# YTN1-E608-WIFI_V1_6432.net
KiCad netlist of a schematic drawn in Altium Designer
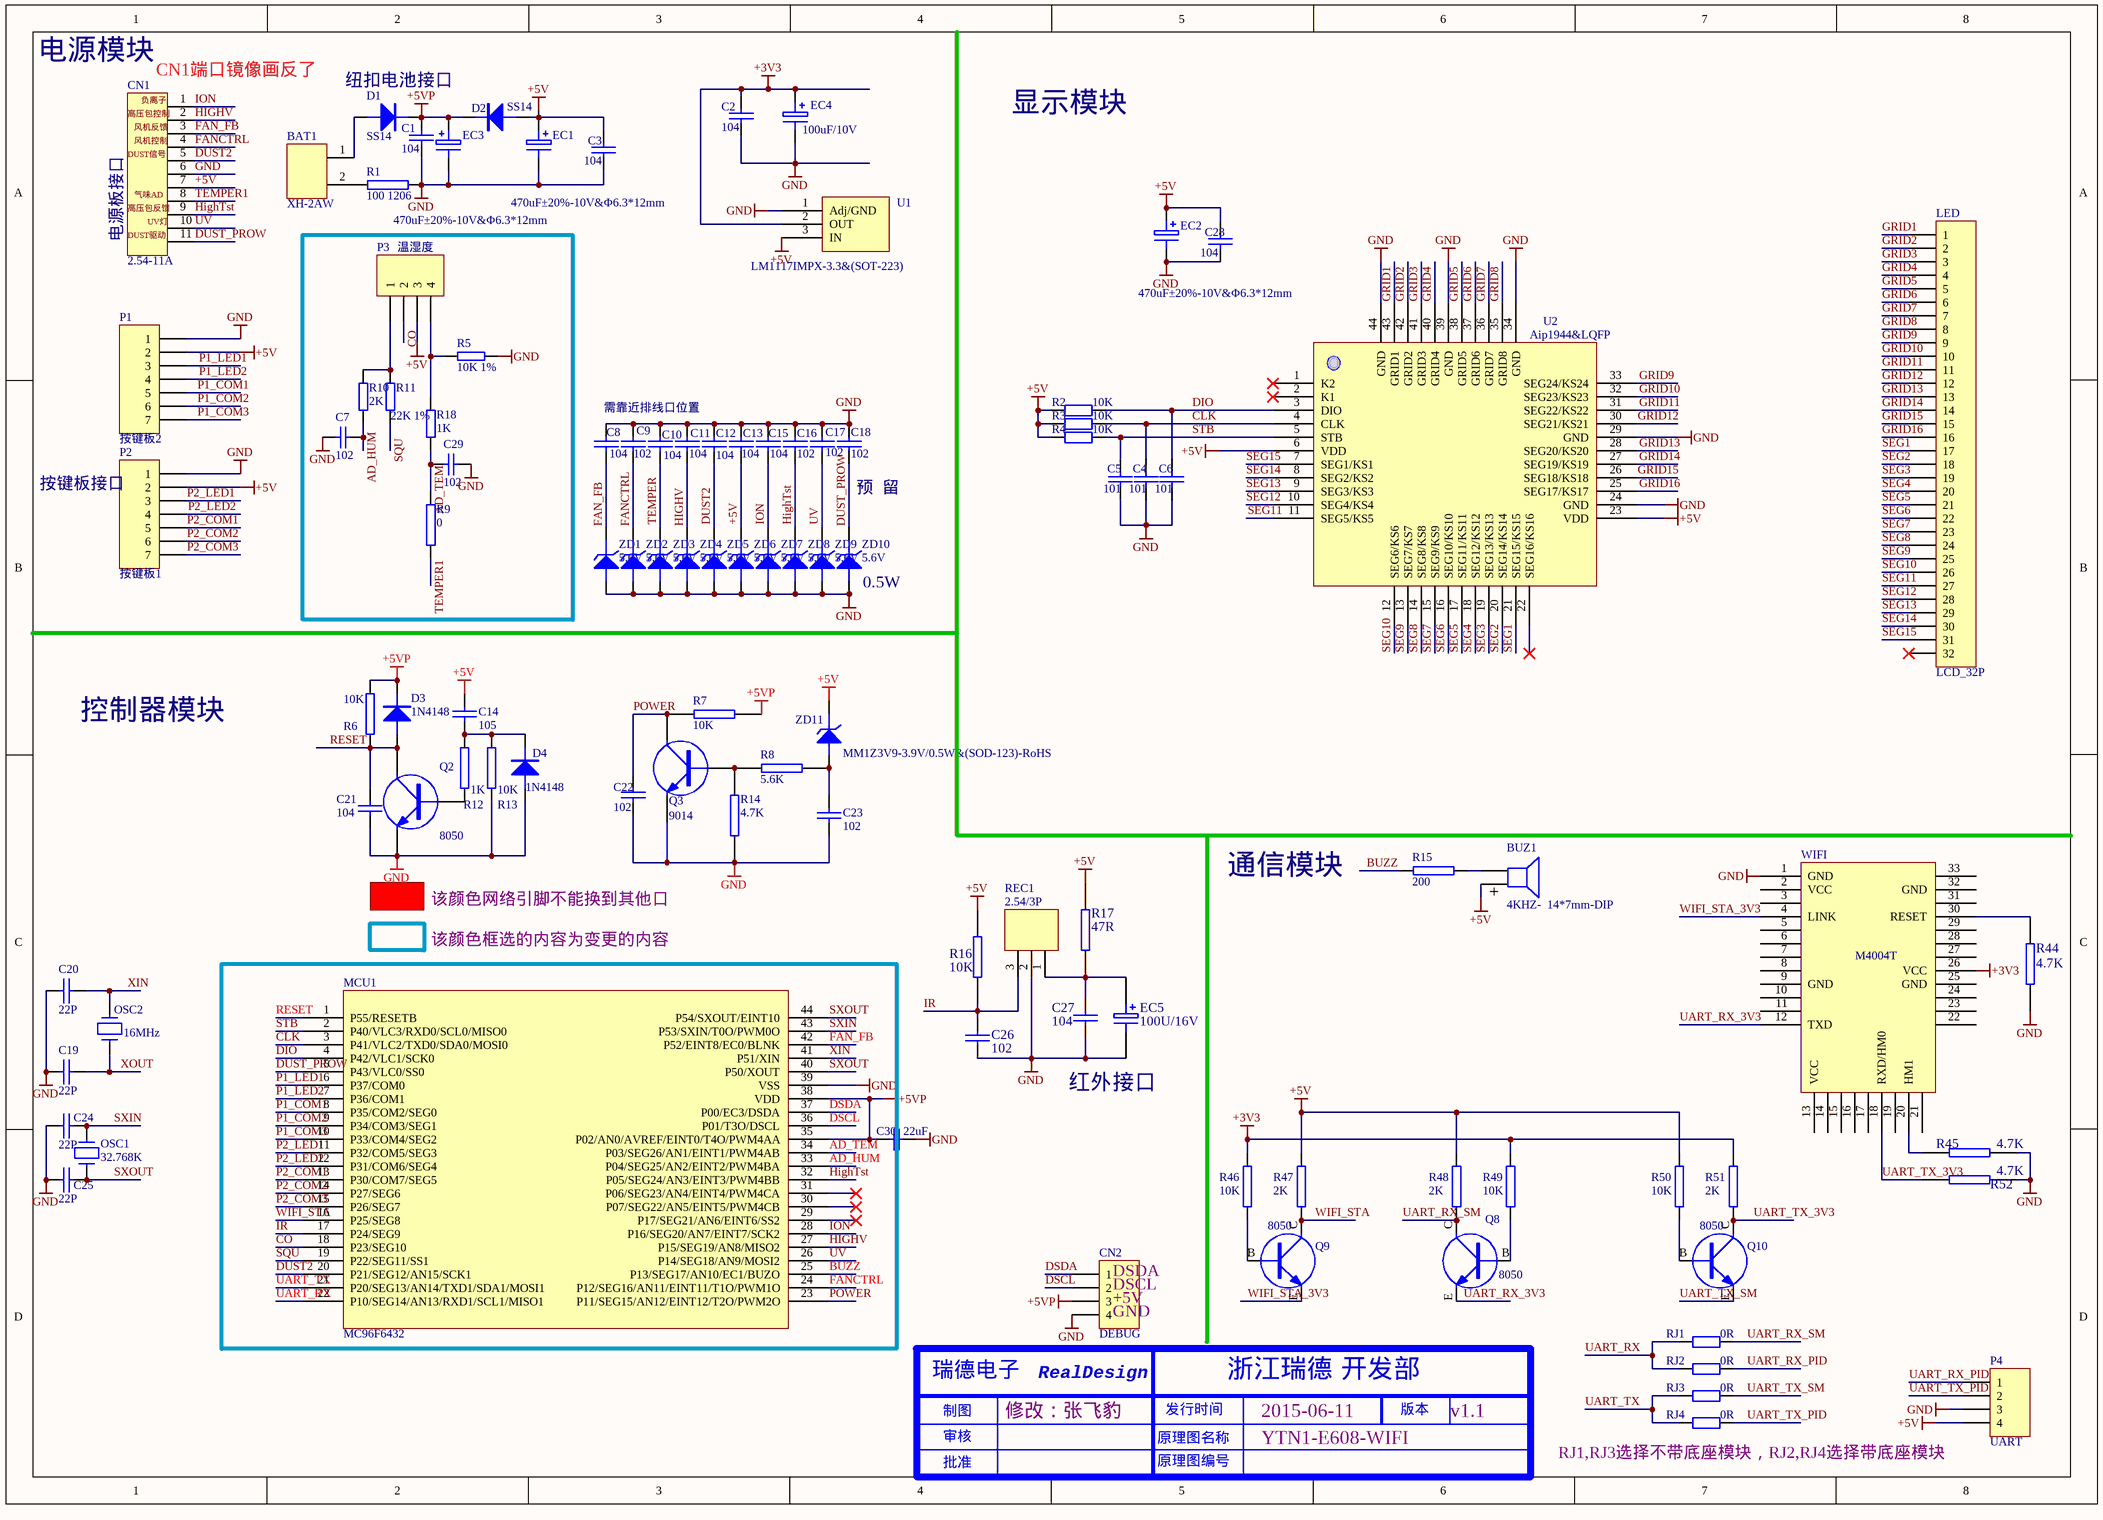
[diagram p0: YTN1-E608-WIFI_V1_6432..schdoc]

(export (version "E")
  (design (tool "Eeschema 10.0.6"))
  (components
    (comp (ref "BAT1") (value "XH-2AW") (footprint "XH-2AW-1") (libsource (lib "*") (part "250-2A")))
    (comp (ref "BUZ1")
      (value "4KHZ-  14*7mm-DIP")
      (footprint "BUZ4K-BCE")
      (libsource (lib "*") (part "SPEAKER"))
    )
    (comp (ref "C1") (value "104") (footprint "0805C") (libsource (lib "*") (part "CAP")))
    (comp (ref "C2") (value "104") (footprint "0805C") (libsource (lib "*") (part "CAP")))
    (comp (ref "C3") (value "104") (footprint "0805C") (libsource (lib "*") (part "CAP")))
    (comp (ref "C4")
      (value "101")
      (footprint "0805C")
      (description "瓷片电容、独石电容")
      (libsource (lib "*") (part "CAP"))
    )
    (comp (ref "C5")
      (value "101")
      (footprint "0805C")
      (description "瓷片电容、独石电容")
      (libsource (lib "*") (part "CAP"))
    )
    (comp (ref "C6")
      (value "101")
      (footprint "0805C")
      (description "瓷片电容、独石电容")
      (libsource (lib "*") (part "CAP"))
    )
    (comp (ref "C7")
      (value "102")
      (footprint "C0805")
      (description "Capacitor")
      (fields (field (name "PUBLISHER") "Altium Limited"))
      (libsource (lib "*") (part "Cap"))
    )
    (comp (ref "C8")
      (value "104")
      (footprint "0805C")
      (description "瓷片电容、独石电容")
      (libsource (lib "*") (part "CAP"))
    )
    (comp (ref "C9")
      (value "102")
      (footprint "0805C")
      (description "瓷片电容、独石电容")
      (libsource (lib "*") (part "CAP"))
    )
    (comp (ref "C10")
      (value "104")
      (footprint "0805C")
      (description "瓷片电容、独石电容")
      (libsource (lib "*") (part "CAP"))
    )
    (comp (ref "C11")
      (value "104")
      (footprint "0805C")
      (description "瓷片电容、独石电容")
      (libsource (lib "*") (part "CAP"))
    )
    (comp (ref "C12")
      (value "104")
      (footprint "0805C")
      (description "瓷片电容、独石电容")
      (libsource (lib "*") (part "CAP"))
    )
    (comp (ref "C13")
      (value "104")
      (footprint "0805C")
      (description "瓷片电容、独石电容")
      (libsource (lib "*") (part "CAP"))
    )
    (comp (ref "C14")
      (value "105")
      (footprint "0805C")
      (description "瓷片电容、独石电容")
      (libsource (lib "*") (part "CAP"))
    )
    (comp (ref "C15")
      (value "104")
      (footprint "0805C")
      (description "瓷片电容、独石电容")
      (libsource (lib "*") (part "CAP"))
    )
    (comp (ref "C16")
      (value "102")
      (footprint "0805C")
      (description "瓷片电容、独石电容")
      (libsource (lib "*") (part "CAP"))
    )
    (comp (ref "C17")
      (value "102")
      (footprint "0805C")
      (description "瓷片电容、独石电容")
      (libsource (lib "*") (part "CAP"))
    )
    (comp (ref "C18")
      (value "102")
      (footprint "0805C")
      (description "瓷片电容、独石电容")
      (libsource (lib "*") (part "CAP"))
    )
    (comp (ref "C19")
      (value "22P")
      (footprint "0805C")
      (description "瓷片电容、独石电容")
      (libsource (lib "") (part "CAP_1"))
    )
    (comp (ref "C20")
      (value "22P")
      (footprint "0805C")
      (description "瓷片电容、独石电容")
      (libsource (lib "") (part "CAP_1"))
    )
    (comp (ref "C21")
      (value "104")
      (footprint "0805C")
      (description "瓷片电容、独石电容")
      (libsource (lib "*") (part "CAP"))
    )
    (comp (ref "C22")
      (value "102")
      (footprint "0805C")
      (description "瓷片电容、独石电容")
      (libsource (lib "*") (part "CAP"))
    )
    (comp (ref "C23")
      (value "102")
      (footprint "0805C")
      (description "瓷片电容、独石电容")
      (libsource (lib "*") (part "CAP"))
    )
    (comp (ref "C24") (value "22P") (footprint "0805C") (libsource (lib "*") (part "CAP")))
    (comp (ref "C25") (value "22P") (footprint "0805C") (libsource (lib "*") (part "CAP")))
    (comp (ref "C26")
      (value "102")
      (footprint "0805C")
      (description "Capacitor")
      (libsource (lib "") (part "CAP_2"))
    )
    (comp (ref "C27")
      (value "104")
      (footprint "0805C")
      (description "Capacitor")
      (libsource (lib "") (part "CAP_2"))
    )
    (comp (ref "C28") (value "104") (footprint "0805C") (libsource (lib "*") (part "CAP")))
    (comp (ref "C29")
      (value "102")
      (footprint "C0805")
      (description "Capacitor")
      (fields (field (name "PUBLISHER") "Altium Limited"))
      (libsource (lib "*") (part "Cap"))
    )
    (comp (ref "C30")
      (value "22uF")
      (footprint "C0805")
      (description "Capacitor")
      (fields (field (name "PUBLISHER") "Altium Limited"))
      (libsource (lib "*") (part "Cap"))
    )
    (comp (ref "CN1") (value "2.54-11A") (footprint "XH-11AW-1") (libsource (lib "*") (part "3.96-11A")))
    (comp (ref "CN2")
      (value "DEBUG")
      (footprint "XH-4AW-1")
      (description "Header, 4-Pin")
      (fields (field (name "PUBLISHER") "Altium Limited"))
      (libsource (lib "*") (part "Header 4"))
    )
    (comp (ref "D1")
      (value "SS14")
      (footprint "SMA")
      (description "整流二极管、开关二极管、肖特基二极管、快恢复二极管")
      (libsource (lib "*") (part "DIODE"))
    )
    (comp (ref "D2")
      (value "SS14")
      (footprint "SMA")
      (description "整流二极管、开关二极管、肖特基二极管、快恢复二极管")
      (libsource (lib "*") (part "DIODE"))
    )
    (comp (ref "D3")
      (value "1N4148")
      (footprint "SOD-123")
      (description "整流二极管、开关二极管、肖特基二极管、快恢复二极管")
      (libsource (lib "*") (part "DIODE"))
    )
    (comp (ref "D4")
      (value "1N4148")
      (footprint "SOD-123")
      (description "整流二极管、开关二极管、肖特基二极管、快恢复二极管")
      (libsource (lib "*") (part "DIODE"))
    )
    (comp (ref "EC1")
      (value "470uF±20%-10V&Φ6.3*12mm")
      (footprint "470UF10V-AI")
      (description "电解电容正极为\"1\"号脚")
      (libsource (lib "*") (part "ELECTRO"))
    )
    (comp (ref "EC2")
      (value "470uF±20%-10V&Φ6.3*12mm")
      (footprint "470UF10V-AI")
      (description "电解电容正极为\"1\"号脚")
      (libsource (lib "*") (part "ELECTRO"))
    )
    (comp (ref "EC3")
      (value "470uF±20%-10V&Φ6.3*12mm")
      (footprint "470UF10V-AI")
      (libsource (lib "*") (part "ELECTRO1"))
    )
    (comp (ref "EC4") (value "100uF/10V") (footprint "100UF10V-AI") (libsource (lib "*") (part "ELECTRO1")))
    (comp (ref "EC5")
      (value "100U/16V")
      (footprint "100UF16V-AI")
      (description "Electrolytic Capacitor")
      (libsource (lib "") (part "ELECTRO1_1"))
    )
    (comp (ref "LED") (value "LCD_32P") (footprint "HYH") (libsource (lib "*") (part "LCD_32P")))
    (comp (ref "MCU1") (value "MC96F6432") (footprint "QFP44-2") (libsource (lib "*") (part "MC96F9432")))
    (comp (ref "OSC1")
      (value "32.768K")
      (footprint "32.768J")
      (description "Crystal")
      (libsource (lib "") (part "CRYSTAL_1"))
    )
    (comp (ref "OSC2")
      (value "16MHz")
      (footprint "CSA4.19MG")
      (description "Crystal")
      (libsource (lib "*") (part "CRYSTAL"))
    )
    (comp (ref "P1")
      (value "按键板2")
      (footprint "XH-7AW-1")
      (description "Header, 7-Pin")
      (fields (field (name "PUBLISHER") "Altium Limited"))
      (libsource (lib "*") (part "Header 7"))
    )
    (comp (ref "P2")
      (value "按键板1")
      (footprint "XH-7AW-1")
      (description "Header, 7-Pin")
      (fields (field (name "PUBLISHER") "Altium Limited"))
      (libsource (lib "*") (part "Header 7"))
    )
    (comp (ref "P3")
      (value "温湿度")
      (footprint "HDR1X4")
      (description "Header, 4-Pin")
      (fields (field (name "PUBLISHER") "Altium Limited"))
      (libsource (lib "") (part "Header 4_1"))
    )
    (comp (ref "P4")
      (value "UART")
      (footprint "XH-4AW-1")
      (description "Header, 4-Pin")
      (fields (field (name "PUBLISHER") "Altium Limited"))
      (libsource (lib "*") (part "Header 4"))
    )
    (comp (ref "Q2")
      (value "8050")
      (footprint "SOT-23-S")
      (description "晶体管")
      (libsource (lib "*") (part "NPN"))
    )
    (comp (ref "Q3")
      (value "9014")
      (footprint "SOT-23-S")
      (description "晶体管")
      (libsource (lib "*") (part "NPN"))
    )
    (comp (ref "Q8")
      (value "8050")
      (footprint "SOT-23-S")
      (description "NPN Transistor")
      (libsource (lib "") (part "NPN_1"))
    )
    (comp (ref "Q9")
      (value "8050")
      (footprint "SOT-23-S")
      (description "NPN Transistor")
      (libsource (lib "") (part "NPN_1"))
    )
    (comp (ref "Q10")
      (value "8050")
      (footprint "SOT-23-S")
      (description "NPN Transistor")
      (libsource (lib "") (part "NPN_1"))
    )
    (comp (ref "R1") (value "100 1206") (footprint "1206R") (libsource (lib "*") (part "RES2")))
    (comp (ref "R2")
      (value "10K")
      (footprint "0805R")
      (description "Resistor")
      (fields (field (name "Comment") "Res2") (field (name "PUBLISHER") "Altium Limited"))
      (libsource (lib "") (part "Res2_1"))
    )
    (comp (ref "R3")
      (value "10K")
      (footprint "0805R")
      (description "Resistor")
      (fields (field (name "Comment") "Res2") (field (name "PUBLISHER") "Altium Limited"))
      (libsource (lib "") (part "Res2_1"))
    )
    (comp (ref "R4")
      (value "10K")
      (footprint "0805R")
      (description "Resistor")
      (fields (field (name "Comment") "Res2") (field (name "PUBLISHER") "Altium Limited"))
      (libsource (lib "*") (part "Res2"))
    )
    (comp (ref "R5")
      (value "10K 1%")
      (footprint "0805r")
      (description "RESISTOR")
      (libsource (lib "") (part "RES2_V_1"))
    )
    (comp (ref "R6") (value "10K") (footprint "0805R") (libsource (lib "*") (part "RES2")))
    (comp (ref "R7") (value "10K") (footprint "0805R") (libsource (lib "*") (part "R")))
    (comp (ref "R8") (value "5.6K") (footprint "0805R") (libsource (lib "*") (part "R")))
    (comp (ref "R9") (value "0") (footprint "0805R") (libsource (lib "*") (part "RES2")))
    (comp (ref "R10")
      (value "2K")
      (footprint "0805r")
      (description "RESISTOR")
      (libsource (lib "*") (part "RES2_V"))
    )
    (comp (ref "R11")
      (value "22K 1%")
      (footprint "0805r")
      (description "RESISTOR")
      (libsource (lib "*") (part "RES2_V"))
    )
    (comp (ref "R12") (value "1K") (footprint "0805R") (libsource (lib "*") (part "RES2")))
    (comp (ref "R13") (value "10K") (footprint "0805R") (libsource (lib "*") (part "RES2")))
    (comp (ref "R14") (value "4.7K") (footprint "0805R") (libsource (lib "*") (part "R")))
    (comp (ref "R15") (value "200") (footprint "0805R") (libsource (lib "*") (part "RES2")))
    (comp (ref "R16") (value "10K") (footprint "0805R") (libsource (lib "") (part "RES2_1")))
    (comp (ref "R17") (value "47R") (footprint "0805-1") (libsource (lib "") (part "RES2_1")))
    (comp (ref "R18")
      (value "1K")
      (footprint "0805r")
      (description "RESISTOR")
      (libsource (lib "*") (part "RES2_V"))
    )
    (comp (ref "R44") (value "4.7K") (footprint "0805R") (libsource (lib "") (part "RES2_1")))
    (comp (ref "R45") (value "4.7K") (footprint "0805R") (libsource (lib "") (part "RES2_1")))
    (comp (ref "R46") (value "10K") (footprint "0805R") (libsource (lib "*") (part "RES2")))
    (comp (ref "R47") (value "2K") (footprint "0805R") (libsource (lib "*") (part "RES2")))
    (comp (ref "R48") (value "2K") (footprint "0805R") (libsource (lib "*") (part "RES2")))
    (comp (ref "R49") (value "10K") (footprint "0805R") (libsource (lib "*") (part "RES2")))
    (comp (ref "R50") (value "10K") (footprint "0805R") (libsource (lib "*") (part "RES2")))
    (comp (ref "R51") (value "2K") (footprint "0805R") (libsource (lib "*") (part "RES2")))
    (comp (ref "R52") (value "4.7K") (footprint "0805R") (libsource (lib "") (part "RES2_1")))
    (comp (ref "REC1") (value "2.54/3P") (footprint "XH-3AW-1") (libsource (lib "*") (part "3.96-3A")))
    (comp (ref "RJ1")
      (value "0R")
      (footprint "0805R")
      (description "Resistor")
      (fields (field (name "PUBLISHER") "Altium Limited"))
      (libsource (lib "*") (part "Res2"))
    )
    (comp (ref "RJ2")
      (value "0R")
      (footprint "0805R")
      (description "Resistor")
      (fields (field (name "PUBLISHER") "Altium Limited"))
      (libsource (lib "*") (part "Res2"))
    )
    (comp (ref "RJ3")
      (value "0R")
      (footprint "0805R")
      (description "Resistor")
      (fields (field (name "PUBLISHER") "Altium Limited"))
      (libsource (lib "*") (part "Res2"))
    )
    (comp (ref "RJ4")
      (value "0R")
      (footprint "0805R")
      (description "Resistor")
      (fields (field (name "PUBLISHER") "Altium Limited"))
      (libsource (lib "*") (part "Res2"))
    )
    (comp (ref "U1") (value "LM1117IMPX-3.3&(SOT-223)") (libsource (lib "*") (part "LM1117-3.3V")))
    (comp (ref "U2") (value "Aip1944&LQFP") (footprint "QFP44") (libsource (lib "*") (part "Aip1944&LQFP")))
    (comp (ref "WIFI") (value "M4004T") (footprint "M4004T") (libsource (lib "*") (part "WIFI")))
    (comp (ref "ZD1") (value "5.6V") (footprint "SOD-123") (libsource (lib "*") (part "ZD")))
    (comp (ref "ZD2") (value "5.6V") (footprint "SOD-123") (libsource (lib "*") (part "ZD")))
    (comp (ref "ZD3") (value "5.6V") (footprint "SOD-123") (libsource (lib "*") (part "ZD")))
    (comp (ref "ZD4") (value "5.6V") (footprint "SOD-123") (libsource (lib "*") (part "ZD")))
    (comp (ref "ZD5") (value "5.6V") (footprint "SOD-123") (libsource (lib "*") (part "ZD")))
    (comp (ref "ZD6") (value "5.6V") (footprint "SOD-123") (libsource (lib "*") (part "ZD")))
    (comp (ref "ZD7") (value "5.6V") (footprint "SOD-123") (libsource (lib "*") (part "ZD")))
    (comp (ref "ZD8") (value "5.6V") (footprint "SOD-123") (libsource (lib "*") (part "ZD")))
    (comp (ref "ZD9") (value "5.6V") (footprint "SOD-123") (libsource (lib "*") (part "ZD")))
    (comp (ref "ZD10") (value "5.6V") (footprint "SOD-123") (libsource (lib "*") (part "ZD")))
    (comp (ref "ZD11")
      (value "MM1Z3V9-3.9V/0.5W&(SOD-123)-RoHS")
      (footprint "SOD-123")
      (libsource (lib "*") (part "ZD"))
    )
  )
  (nets
    (net (code "1") (name "+3V3") (class "Default")
      (node (ref "C2") (pin "1") (pintype "passive"))
      (node (ref "EC4") (pin "1") (pintype "passive"))
      (node (ref "R46") (pin "1") (pintype "passive"))
      (node (ref "R49") (pin "1") (pintype "passive"))
      (node (ref "R51") (pin "1") (pintype "passive"))
      (node (ref "U1") (pin "2") (pinfunction "OUT_2") (pintype "passive"))
      (node (ref "WIFI") (pin "26") (pinfunction "VCC_26") (pintype "passive"))
    )
    (net (code "2") (name "+5V") (class "Default")
      (node (ref "BUZ1") (pin "1") (pinfunction "1_1") (pintype "passive"))
      (node (ref "C13") (pin "2") (pintype "passive"))
      (node (ref "C14") (pin "1") (pintype "passive"))
      (node (ref "C28") (pin "1") (pintype "passive"))
      (node (ref "C3") (pin "1") (pintype "passive"))
      (node (ref "CN1") (pin "7") (pinfunction "7_7") (pintype "passive"))
      (node (ref "D2") (pin "A") (pintype "passive"))
      (node (ref "EC1") (pin "1") (pintype "passive"))
      (node (ref "EC2") (pin "1") (pintype "passive"))
      (node (ref "P1") (pin "2") (pinfunction "2_2") (pintype "passive"))
      (node (ref "P2") (pin "2") (pinfunction "2_2") (pintype "passive"))
      (node (ref "P3") (pin "3") (pinfunction "3_3") (pintype "passive"))
      (node (ref "P4") (pin "4") (pinfunction "4_4") (pintype "passive"))
      (node (ref "R16") (pin "2") (pinfunction "2_2") (pintype "passive"))
      (node (ref "R17") (pin "2") (pinfunction "2_2") (pintype "passive"))
      (node (ref "R2") (pin "2") (pinfunction "2_2") (pintype "passive"))
      (node (ref "R3") (pin "2") (pinfunction "2_2") (pintype "passive"))
      (node (ref "R4") (pin "1") (pinfunction "1_1") (pintype "passive"))
      (node (ref "R47") (pin "1") (pintype "passive"))
      (node (ref "R48") (pin "1") (pintype "passive"))
      (node (ref "R50") (pin "1") (pintype "passive"))
      (node (ref "U1") (pin "3") (pinfunction "IN_3") (pintype "passive"))
      (node (ref "U2") (pin "23") (pinfunction "VDD_23") (pintype "passive"))
      (node (ref "U2") (pin "6") (pinfunction "VDD_6") (pintype "passive"))
      (node (ref "ZD11") (pin "K") (pintype "passive"))
      (node (ref "ZD6") (pin "K") (pintype "passive"))
    )
    (net (code "3") (name "+5VP") (class "Default")
      (node (ref "C1") (pin "1") (pintype "passive"))
      (node (ref "C30") (pin "2") (pinfunction "2_2") (pintype "passive"))
      (node (ref "CN2") (pin "3") (pinfunction "3_3") (pintype "passive"))
      (node (ref "D1") (pin "K") (pintype "passive"))
      (node (ref "D2") (pin "K") (pintype "passive"))
      (node (ref "D3") (pin "K") (pintype "passive"))
      (node (ref "EC3") (pin "1") (pintype "passive"))
      (node (ref "MCU1") (pin "35") (pinfunction "P02/AN0/AVREF/EINT0/T4O/PWM4AA_35") (pintype "passive"))
      (node (ref "MCU1") (pin "38") (pinfunction "VDD_38") (pintype "passive"))
      (node (ref "R6") (pin "2") (pintype "passive"))
      (node (ref "R7") (pin "1") (pinfunction "1_1") (pintype "passive"))
    )
    (net (code "4") (name "/AD_HUM") (class "Default")
      (node (ref "C7") (pin "1") (pinfunction "1_1") (pintype "passive"))
      (node (ref "MCU1") (pin "33") (pinfunction "P04/SEG25/AN2/EINT2/PWM4BA_33") (pintype "passive"))
      (node (ref "R10") (pin "2") (pinfunction "2_2") (pintype "passive"))
    )
    (net (code "5") (name "/AD_TEM") (class "Default")
      (node (ref "C29") (pin "2") (pinfunction "2_2") (pintype "passive"))
      (node (ref "MCU1") (pin "34") (pinfunction "P03/SEG26/AN1/EINT1/PWM4AB_34") (pintype "passive"))
      (node (ref "R18") (pin "2") (pinfunction "2_2") (pintype "passive"))
      (node (ref "R9") (pin "1") (pintype "passive"))
    )
    (net (code "6") (name "/BUZZ") (class "Default")
      (node (ref "MCU1") (pin "25") (pinfunction "P13/SEG17/AN10/EC1/BUZO_25") (pintype "passive"))
      (node (ref "R15") (pin "1") (pintype "passive"))
    )
    (net (code "7") (name "/CLK") (class "Default")
      (node (ref "C4") (pin "1") (pintype "passive"))
      (node (ref "MCU1") (pin "3") (pinfunction "P41/VLC2/TXD0/SDA0/MOSI0_3") (pintype "passive"))
      (node (ref "R3") (pin "1") (pinfunction "1_1") (pintype "passive"))
      (node (ref "U2") (pin "4") (pinfunction "CLK_4") (pintype "passive"))
    )
    (net (code "8") (name "/CO") (class "Default")
      (node (ref "MCU1") (pin "18") (pinfunction "P23/SEG10_18") (pintype "passive"))
      (node (ref "P3") (pin "2") (pinfunction "2_2") (pintype "passive"))
    )
    (net (code "9") (name "/DIO") (class "Default")
      (node (ref "C6") (pin "1") (pintype "passive"))
      (node (ref "MCU1") (pin "4") (pinfunction "P42/VLC1/SCK0_4") (pintype "passive"))
      (node (ref "R2") (pin "1") (pinfunction "1_1") (pintype "passive"))
      (node (ref "U2") (pin "3") (pinfunction "DIO_3") (pintype "passive"))
    )
    (net (code "10") (name "/DSCL") (class "Default")
      (node (ref "CN2") (pin "2") (pinfunction "2_2") (pintype "passive"))
      (node (ref "MCU1") (pin "36") (pinfunction "P01/T3O/DSCL_36") (pintype "passive"))
    )
    (net (code "11") (name "/DSDA") (class "Default")
      (node (ref "CN2") (pin "1") (pinfunction "1_1") (pintype "passive"))
      (node (ref "MCU1") (pin "37") (pinfunction "P00/EC3/DSDA_37") (pintype "passive"))
    )
    (net (code "12") (name "/DUST2") (class "Default")
      (node (ref "C12") (pin "2") (pintype "passive"))
      (node (ref "CN1") (pin "5") (pinfunction "5_5") (pintype "passive"))
      (node (ref "MCU1") (pin "20") (pinfunction "P21/SEG12/AN15/SCK1_20") (pintype "passive"))
      (node (ref "ZD5") (pin "K") (pintype "passive"))
    )
    (net (code "13") (name "/DUST_PROW") (class "Default")
      (node (ref "C18") (pin "2") (pintype "passive"))
      (node (ref "CN1") (pin "11") (pinfunction "11_11") (pintype "passive"))
      (node (ref "MCU1") (pin "5") (pinfunction "P43/VLC0/SS0_5") (pintype "passive"))
      (node (ref "ZD10") (pin "K") (pintype "passive"))
    )
    (net (code "16") (name "/FANCTRL") (class "Default")
      (node (ref "C9") (pin "2") (pintype "passive"))
      (node (ref "CN1") (pin "4") (pinfunction "4_4") (pintype "passive"))
      (node (ref "MCU1") (pin "24") (pinfunction "P12/SEG16/AN11/EINT11/T1O/PWM1O_24") (pintype "passive"))
      (node (ref "ZD2") (pin "K") (pintype "passive"))
    )
    (net (code "17") (name "/FAN_FB") (class "Default")
      (node (ref "C8") (pin "2") (pintype "passive"))
      (node (ref "CN1") (pin "3") (pinfunction "3_3") (pintype "passive"))
      (node (ref "MCU1") (pin "42") (pinfunction "P52/EINT8/EC0/BLNK_42") (pintype "passive"))
      (node (ref "ZD1") (pin "K") (pintype "passive"))
    )
    (net (code "18") (name "/GRID1") (class "Default")
      (node (ref "LED") (pin "1") (pinfunction "1_1") (pintype "passive"))
      (node (ref "U2") (pin "43") (pinfunction "GRID1_43") (pintype "passive"))
    )
    (net (code "19") (name "/GRID2") (class "Default")
      (node (ref "LED") (pin "2") (pinfunction "2_2") (pintype "passive"))
      (node (ref "U2") (pin "42") (pinfunction "GRID2_42") (pintype "passive"))
    )
    (net (code "20") (name "/GRID3") (class "Default")
      (node (ref "LED") (pin "3") (pinfunction "3_3") (pintype "passive"))
      (node (ref "U2") (pin "41") (pinfunction "GRID3_41") (pintype "passive"))
    )
    (net (code "21") (name "/GRID4") (class "Default")
      (node (ref "LED") (pin "4") (pinfunction "4_4") (pintype "passive"))
      (node (ref "U2") (pin "40") (pinfunction "GRID4_40") (pintype "passive"))
    )
    (net (code "22") (name "/GRID5") (class "Default")
      (node (ref "LED") (pin "5") (pinfunction "5_5") (pintype "passive"))
      (node (ref "U2") (pin "38") (pinfunction "GRID5_38") (pintype "passive"))
    )
    (net (code "23") (name "/GRID6") (class "Default")
      (node (ref "LED") (pin "6") (pinfunction "6_6") (pintype "passive"))
      (node (ref "U2") (pin "37") (pinfunction "GRID6_37") (pintype "passive"))
    )
    (net (code "24") (name "/GRID7") (class "Default")
      (node (ref "LED") (pin "7") (pinfunction "7_7") (pintype "passive"))
      (node (ref "U2") (pin "36") (pinfunction "GRID7_36") (pintype "passive"))
    )
    (net (code "25") (name "/GRID8") (class "Default")
      (node (ref "LED") (pin "8") (pinfunction "8_8") (pintype "passive"))
      (node (ref "U2") (pin "35") (pinfunction "GRID8_35") (pintype "passive"))
    )
    (net (code "26") (name "/GRID9") (class "Default")
      (node (ref "LED") (pin "9") (pinfunction "9_9") (pintype "passive"))
      (node (ref "U2") (pin "33") (pinfunction "SEG24/KS24_33") (pintype "passive"))
    )
    (net (code "27") (name "/GRID10") (class "Default")
      (node (ref "LED") (pin "10") (pinfunction "10_10") (pintype "passive"))
      (node (ref "U2") (pin "32") (pinfunction "SEG23/KS23_32") (pintype "passive"))
    )
    (net (code "28") (name "/GRID11") (class "Default")
      (node (ref "LED") (pin "11") (pinfunction "11_11") (pintype "passive"))
      (node (ref "U2") (pin "31") (pinfunction "SEG22/KS22_31") (pintype "passive"))
    )
    (net (code "29") (name "/GRID12") (class "Default")
      (node (ref "LED") (pin "12") (pinfunction "12_12") (pintype "passive"))
      (node (ref "U2") (pin "30") (pinfunction "SEG21/KS21_30") (pintype "passive"))
    )
    (net (code "30") (name "/GRID13") (class "Default")
      (node (ref "LED") (pin "13") (pinfunction "13_13") (pintype "passive"))
      (node (ref "U2") (pin "28") (pinfunction "SEG20/KS20_28") (pintype "passive"))
    )
    (net (code "31") (name "/GRID14") (class "Default")
      (node (ref "LED") (pin "14") (pinfunction "14_14") (pintype "passive"))
      (node (ref "U2") (pin "27") (pinfunction "SEG19/KS19_27") (pintype "passive"))
    )
    (net (code "32") (name "/GRID15") (class "Default")
      (node (ref "LED") (pin "15") (pinfunction "15_15") (pintype "passive"))
      (node (ref "U2") (pin "26") (pinfunction "SEG18/KS18_26") (pintype "passive"))
    )
    (net (code "33") (name "/GRID16") (class "Default")
      (node (ref "LED") (pin "16") (pinfunction "16_16") (pintype "passive"))
      (node (ref "U2") (pin "25") (pinfunction "SEG17/KS17_25") (pintype "passive"))
    )
    (net (code "34") (name "/HIGHV") (class "Default")
      (node (ref "C11") (pin "2") (pintype "passive"))
      (node (ref "CN1") (pin "2") (pinfunction "2_2") (pintype "passive"))
      (node (ref "MCU1") (pin "27") (pinfunction "P15/SEG19/AN8/MISO2_27") (pintype "passive"))
      (node (ref "ZD4") (pin "K") (pintype "passive"))
    )
    (net (code "35") (name "/HighTst") (class "Default")
      (node (ref "C16") (pin "2") (pintype "passive"))
      (node (ref "CN1") (pin "9") (pinfunction "9_9") (pintype "passive"))
      (node (ref "MCU1") (pin "32") (pinfunction "P05/SEG24/AN3/EINT3/PWM4BB_32") (pintype "passive"))
      (node (ref "ZD8") (pin "K") (pintype "passive"))
    )
    (net (code "36") (name "/ION") (class "Default")
      (node (ref "C15") (pin "2") (pintype "passive"))
      (node (ref "CN1") (pin "1") (pinfunction "1_1") (pintype "passive"))
      (node (ref "MCU1") (pin "28") (pinfunction "P16/SEG20/AN7/EINT7/SCK2_28") (pintype "passive"))
      (node (ref "ZD7") (pin "K") (pintype "passive"))
    )
    (net (code "37") (name "/IR") (class "Default")
      (node (ref "C26") (pin "1") (pinfunction "1_1") (pintype "passive"))
      (node (ref "MCU1") (pin "17") (pinfunction "P24/SEG9_17") (pintype "passive"))
      (node (ref "R16") (pin "1") (pinfunction "1_1") (pintype "passive"))
      (node (ref "REC1") (pin "3") (pinfunction "20_3") (pintype "passive"))
    )
    (net (code "38") (name "/P1_COM1") (class "Default")
      (node (ref "MCU1") (pin "8") (pinfunction "P35/COM2/SEG0_8") (pintype "passive"))
      (node (ref "P1") (pin "5") (pinfunction "5_5") (pintype "passive"))
    )
    (net (code "39") (name "/P1_COM2") (class "Default")
      (node (ref "MCU1") (pin "9") (pinfunction "P34/COM3/SEG1_9") (pintype "passive"))
      (node (ref "P1") (pin "6") (pinfunction "6_6") (pintype "passive"))
    )
    (net (code "40") (name "/P1_COM3") (class "Default")
      (node (ref "MCU1") (pin "10") (pinfunction "P33/COM4/SEG2_10") (pintype "passive"))
      (node (ref "P1") (pin "7") (pinfunction "7_7") (pintype "passive"))
    )
    (net (code "41") (name "/P1_LED1") (class "Default")
      (node (ref "MCU1") (pin "6") (pinfunction "P37/COM0_6") (pintype "passive"))
      (node (ref "P1") (pin "3") (pinfunction "3_3") (pintype "passive"))
    )
    (net (code "42") (name "/P1_LED2") (class "Default")
      (node (ref "MCU1") (pin "7") (pinfunction "P36/COM1_7") (pintype "passive"))
      (node (ref "P1") (pin "4") (pinfunction "4_4") (pintype "passive"))
    )
    (net (code "43") (name "/P2_COM1") (class "Default")
      (node (ref "MCU1") (pin "13") (pinfunction "P30/COM7/SEG5_13") (pintype "passive"))
      (node (ref "P2") (pin "5") (pinfunction "5_5") (pintype "passive"))
    )
    (net (code "44") (name "/P2_COM2") (class "Default")
      (node (ref "MCU1") (pin "14") (pinfunction "P27/SEG6_14") (pintype "passive"))
      (node (ref "P2") (pin "6") (pinfunction "6_6") (pintype "passive"))
    )
    (net (code "45") (name "/P2_COM3") (class "Default")
      (node (ref "MCU1") (pin "15") (pinfunction "P26/SEG7_15") (pintype "passive"))
      (node (ref "P2") (pin "7") (pinfunction "7_7") (pintype "passive"))
    )
    (net (code "46") (name "/P2_LED1") (class "Default")
      (node (ref "MCU1") (pin "11") (pinfunction "P32/COM5/SEG3_11") (pintype "passive"))
      (node (ref "P2") (pin "3") (pinfunction "3_3") (pintype "passive"))
    )
    (net (code "47") (name "/P2_LED2") (class "Default")
      (node (ref "MCU1") (pin "12") (pinfunction "P31/COM6/SEG4_12") (pintype "passive"))
      (node (ref "P2") (pin "4") (pinfunction "4_4") (pintype "passive"))
    )
    (net (code "48") (name "/POWER") (class "Default")
      (node (ref "C22") (pin "1") (pintype "passive"))
      (node (ref "MCU1") (pin "23") (pinfunction "P11/SEG15/AN12/EINT12/T2O/PWM2O_23") (pintype "passive"))
      (node (ref "Q3") (pin "C") (pintype "passive"))
      (node (ref "R7") (pin "2") (pinfunction "2_2") (pintype "passive"))
    )
    (net (code "49") (name "/RESET") (class "Default")
      (node (ref "C21") (pin "1") (pintype "passive"))
      (node (ref "D3") (pin "A") (pintype "passive"))
      (node (ref "MCU1") (pin "1") (pinfunction "P55/RESETB_1") (pintype "passive"))
      (node (ref "Q2") (pin "C") (pintype "passive"))
      (node (ref "R6") (pin "1") (pintype "passive"))
    )
    (net (code "50") (name "/SEG1") (class "Default")
      (node (ref "LED") (pin "17") (pinfunction "17_17") (pintype "passive"))
      (node (ref "U2") (pin "21") (pinfunction "SEG15/KS15_21") (pintype "passive"))
    )
    (net (code "51") (name "/SEG2") (class "Default")
      (node (ref "LED") (pin "18") (pinfunction "18_18") (pintype "passive"))
      (node (ref "U2") (pin "20") (pinfunction "SEG14/KS14_20") (pintype "passive"))
    )
    (net (code "52") (name "/SEG3") (class "Default")
      (node (ref "LED") (pin "19") (pinfunction "19_19") (pintype "passive"))
      (node (ref "U2") (pin "19") (pinfunction "SEG13/KS13_19") (pintype "passive"))
    )
    (net (code "53") (name "/SEG4") (class "Default")
      (node (ref "LED") (pin "20") (pinfunction "20_20") (pintype "passive"))
      (node (ref "U2") (pin "18") (pinfunction "SEG12/KS12_18") (pintype "passive"))
    )
    (net (code "54") (name "/SEG5") (class "Default")
      (node (ref "LED") (pin "21") (pinfunction "21_21") (pintype "passive"))
      (node (ref "U2") (pin "17") (pinfunction "SEG11/KS11_17") (pintype "passive"))
    )
    (net (code "55") (name "/SEG6") (class "Default")
      (node (ref "LED") (pin "22") (pinfunction "22_22") (pintype "passive"))
      (node (ref "U2") (pin "16") (pinfunction "SEG10/KS10_16") (pintype "passive"))
    )
    (net (code "56") (name "/SEG7") (class "Default")
      (node (ref "LED") (pin "23") (pinfunction "23_23") (pintype "passive"))
      (node (ref "U2") (pin "15") (pinfunction "SEG9/KS9_15") (pintype "passive"))
    )
    (net (code "57") (name "/SEG8") (class "Default")
      (node (ref "LED") (pin "24") (pinfunction "24_24") (pintype "passive"))
      (node (ref "U2") (pin "14") (pinfunction "SEG8/KS8_14") (pintype "passive"))
    )
    (net (code "58") (name "/SEG9") (class "Default")
      (node (ref "LED") (pin "25") (pinfunction "25_25") (pintype "passive"))
      (node (ref "U2") (pin "13") (pinfunction "SEG7/KS7_13") (pintype "passive"))
    )
    (net (code "59") (name "/SEG10") (class "Default")
      (node (ref "LED") (pin "26") (pinfunction "26_26") (pintype "passive"))
      (node (ref "U2") (pin "12") (pinfunction "SEG6/KS6_12") (pintype "passive"))
    )
    (net (code "60") (name "/SEG11") (class "Default")
      (node (ref "LED") (pin "27") (pinfunction "27_27") (pintype "passive"))
      (node (ref "U2") (pin "11") (pinfunction "SEG5/KS5_11") (pintype "passive"))
    )
    (net (code "61") (name "/SEG12") (class "Default")
      (node (ref "LED") (pin "28") (pinfunction "28_28") (pintype "passive"))
      (node (ref "U2") (pin "10") (pinfunction "SEG4/KS4_10") (pintype "passive"))
    )
    (net (code "62") (name "/SEG13") (class "Default")
      (node (ref "LED") (pin "29") (pinfunction "29_29") (pintype "passive"))
      (node (ref "U2") (pin "9") (pinfunction "SEG3/KS3_9") (pintype "passive"))
    )
    (net (code "63") (name "/SEG14") (class "Default")
      (node (ref "LED") (pin "30") (pinfunction "30_30") (pintype "passive"))
      (node (ref "U2") (pin "8") (pinfunction "SEG2/KS2_8") (pintype "passive"))
    )
    (net (code "64") (name "/SEG15") (class "Default")
      (node (ref "LED") (pin "31") (pinfunction "31_31") (pintype "passive"))
      (node (ref "U2") (pin "7") (pinfunction "SEG1/KS1_7") (pintype "passive"))
    )
    (net (code "65") (name "/SQU") (class "Default")
      (node (ref "MCU1") (pin "19") (pinfunction "P22/SEG11/SS1_19") (pintype "passive"))
      (node (ref "R11") (pin "2") (pinfunction "2_2") (pintype "passive"))
    )
    (net (code "66") (name "/STB") (class "Default")
      (node (ref "C5") (pin "1") (pintype "passive"))
      (node (ref "MCU1") (pin "2") (pinfunction "P40/VLC3/RXD0/SCL0/MISO0_2") (pintype "passive"))
      (node (ref "R4") (pin "2") (pinfunction "2_2") (pintype "passive"))
      (node (ref "U2") (pin "5") (pinfunction "STB_5") (pintype "passive"))
    )
    (net (code "67") (name "/SXIN") (class "Default")
      (node (ref "C24") (pin "2") (pintype "passive"))
      (node (ref "MCU1") (pin "43") (pinfunction "P53/SXIN/T0O/PWM0O_43") (pintype "passive"))
      (node (ref "OSC1") (pin "2") (pinfunction "2_2") (pintype "passive"))
    )
    (net (code "68") (name "/SXOUT") (class "Default")
      (node (ref "C25") (pin "2") (pintype "passive"))
      (node (ref "MCU1") (pin "40") (pinfunction "P50/XOUT_40") (pintype "passive"))
      (node (ref "MCU1") (pin "44") (pinfunction "P54/SXOUT/EINT10_44") (pintype "passive"))
      (node (ref "OSC1") (pin "1") (pinfunction "1_1") (pintype "passive"))
    )
    (net (code "69") (name "/TEMPER") (class "Default")
      (node (ref "C10") (pin "2") (pintype "passive"))
      (node (ref "ZD3") (pin "K") (pintype "passive"))
    )
    (net (code "70") (name "/TEMPER1") (class "Default")
      (node (ref "CN1") (pin "8") (pinfunction "8_8") (pintype "passive"))
      (node (ref "R9") (pin "2") (pintype "passive"))
    )
    (net (code "71") (name "/UART_RX") (class "Default")
      (node (ref "MCU1") (pin "22") (pinfunction "P10/SEG14/AN13/RXD1/SCL1/MISO1_22") (pintype "passive"))
      (node (ref "RJ1") (pin "1") (pinfunction "1_1") (pintype "passive"))
      (node (ref "RJ2") (pin "1") (pinfunction "1_1") (pintype "passive"))
    )
    (net (code "72") (name "/UART_RX_3V3") (class "Default")
      (node (ref "Q8") (pin "E") (pintype "passive"))
      (node (ref "WIFI") (pin "12") (pinfunction "TXD_12") (pintype "passive"))
    )
    (net (code "73") (name "/UART_RX_PID") (class "Default")
      (node (ref "P4") (pin "1") (pinfunction "1_1") (pintype "passive"))
      (node (ref "RJ2") (pin "2") (pinfunction "2_2") (pintype "passive"))
    )
    (net (code "74") (name "/UART_RX_SM") (class "Default")
      (node (ref "Q8") (pin "C") (pintype "passive"))
      (node (ref "R48") (pin "2") (pintype "passive"))
      (node (ref "RJ1") (pin "2") (pinfunction "2_2") (pintype "passive"))
    )
    (net (code "75") (name "/UART_TX") (class "Default")
      (node (ref "MCU1") (pin "21") (pinfunction "P20/SEG13/AN14/TXD1/SDA1/MOSI1_21") (pintype "passive"))
      (node (ref "RJ3") (pin "1") (pinfunction "1_1") (pintype "passive"))
      (node (ref "RJ4") (pin "1") (pinfunction "1_1") (pintype "passive"))
    )
    (net (code "76") (name "/UART_TX_3V3") (class "Default")
      (node (ref "Q10") (pin "C") (pintype "passive"))
      (node (ref "R51") (pin "2") (pintype "passive"))
      (node (ref "R52") (pin "2") (pinfunction "2_2") (pintype "passive"))
      (node (ref "WIFI") (pin "18") (pinfunction "RXD/HM0_18") (pintype "passive"))
    )
    (net (code "77") (name "/UART_TX_PID") (class "Default")
      (node (ref "P4") (pin "2") (pinfunction "2_2") (pintype "passive"))
      (node (ref "RJ4") (pin "2") (pinfunction "2_2") (pintype "passive"))
    )
    (net (code "78") (name "/UART_TX_SM") (class "Default")
      (node (ref "Q10") (pin "E") (pintype "passive"))
      (node (ref "RJ3") (pin "2") (pinfunction "2_2") (pintype "passive"))
    )
    (net (code "79") (name "/UV") (class "Default")
      (node (ref "C17") (pin "2") (pintype "passive"))
      (node (ref "CN1") (pin "10") (pinfunction "10_10") (pintype "passive"))
      (node (ref "MCU1") (pin "26") (pinfunction "P14/SEG18/AN9/MOSI2_26") (pintype "passive"))
      (node (ref "ZD9") (pin "K") (pintype "passive"))
    )
    (net (code "81") (name "/WIFI_STA") (class "Default")
      (node (ref "MCU1") (pin "16") (pinfunction "P25/SEG8_16") (pintype "passive"))
      (node (ref "Q9") (pin "C") (pintype "passive"))
      (node (ref "R47") (pin "2") (pintype "passive"))
    )
    (net (code "82") (name "/WIFI_STA_3V3") (class "Default")
      (node (ref "Q9") (pin "E") (pintype "passive"))
      (node (ref "WIFI") (pin "4") (pinfunction "LINK_4") (pintype "passive"))
    )
    (net (code "83") (name "/XIN") (class "Default")
      (node (ref "C20") (pin "1") (pintype "passive"))
      (node (ref "MCU1") (pin "41") (pinfunction "P51/XIN_41") (pintype "passive"))
      (node (ref "OSC2") (pin "3") (pinfunction "3_3") (pintype "passive"))
    )
    (net (code "84") (name "/XOUT") (class "Default")
      (node (ref "C19") (pin "1") (pintype "passive"))
      (node (ref "OSC2") (pin "1") (pinfunction "1_1") (pintype "passive"))
    )
    (net (code "91") (name "GND") (class "Default")
      (node (ref "C1") (pin "2") (pintype "passive"))
      (node (ref "C10") (pin "1") (pintype "passive"))
      (node (ref "C11") (pin "1") (pintype "passive"))
      (node (ref "C12") (pin "1") (pintype "passive"))
      (node (ref "C13") (pin "1") (pintype "passive"))
      (node (ref "C15") (pin "1") (pintype "passive"))
      (node (ref "C16") (pin "1") (pintype "passive"))
      (node (ref "C17") (pin "1") (pintype "passive"))
      (node (ref "C18") (pin "1") (pintype "passive"))
      (node (ref "C19") (pin "2") (pintype "passive"))
      (node (ref "C2") (pin "2") (pintype "passive"))
      (node (ref "C20") (pin "2") (pintype "passive"))
      (node (ref "C21") (pin "2") (pintype "passive"))
      (node (ref "C22") (pin "2") (pintype "passive"))
      (node (ref "C23") (pin "2") (pintype "passive"))
      (node (ref "C24") (pin "1") (pintype "passive"))
      (node (ref "C25") (pin "1") (pintype "passive"))
      (node (ref "C26") (pin "2") (pinfunction "2_2") (pintype "passive"))
      (node (ref "C27") (pin "2") (pinfunction "2_2") (pintype "passive"))
      (node (ref "C28") (pin "2") (pintype "passive"))
      (node (ref "C29") (pin "1") (pinfunction "1_1") (pintype "passive"))
      (node (ref "C3") (pin "2") (pintype "passive"))
      (node (ref "C30") (pin "1") (pinfunction "1_1") (pintype "passive"))
      (node (ref "C4") (pin "2") (pintype "passive"))
      (node (ref "C5") (pin "2") (pintype "passive"))
      (node (ref "C6") (pin "2") (pintype "passive"))
      (node (ref "C7") (pin "2") (pinfunction "2_2") (pintype "passive"))
      (node (ref "C8") (pin "1") (pintype "passive"))
      (node (ref "C9") (pin "1") (pintype "passive"))
      (node (ref "CN1") (pin "6") (pinfunction "6_6") (pintype "passive"))
      (node (ref "CN2") (pin "4") (pinfunction "4_4") (pintype "passive"))
      (node (ref "D4") (pin "A") (pintype "passive"))
      (node (ref "EC1") (pin "2") (pintype "passive"))
      (node (ref "EC2") (pin "2") (pintype "passive"))
      (node (ref "EC3") (pin "2") (pintype "passive"))
      (node (ref "EC4") (pin "2") (pintype "passive"))
      (node (ref "EC5") (pin "2") (pinfunction "2_2") (pintype "passive"))
      (node (ref "MCU1") (pin "39") (pinfunction "VSS_39") (pintype "passive"))
      (node (ref "P1") (pin "1") (pinfunction "1_1") (pintype "passive"))
      (node (ref "P2") (pin "1") (pinfunction "1_1") (pintype "passive"))
      (node (ref "P4") (pin "3") (pinfunction "3_3") (pintype "passive"))
      (node (ref "Q2") (pin "E") (pintype "passive"))
      (node (ref "Q3") (pin "E") (pintype "passive"))
      (node (ref "R1") (pin "2") (pintype "passive"))
      (node (ref "R13") (pin "1") (pintype "passive"))
      (node (ref "R14") (pin "1") (pinfunction "1_1") (pintype "passive"))
      (node (ref "R44") (pin "2") (pinfunction "2_2") (pintype "passive"))
      (node (ref "R45") (pin "1") (pinfunction "1_1") (pintype "passive"))
      (node (ref "R5") (pin "2") (pinfunction "2_2") (pintype "passive"))
      (node (ref "R52") (pin "1") (pinfunction "1_1") (pintype "passive"))
      (node (ref "REC1") (pin "2") (pinfunction "2_2") (pintype "passive"))
      (node (ref "U1") (pin "1") (pinfunction "Adj/GND_1") (pintype "passive"))
      (node (ref "U2") (pin "24") (pinfunction "GND_24") (pintype "passive"))
      (node (ref "U2") (pin "29") (pinfunction "GND_29") (pintype "passive"))
      (node (ref "U2") (pin "34") (pinfunction "GND_34") (pintype "passive"))
      (node (ref "U2") (pin "39") (pinfunction "GND_39") (pintype "passive"))
      (node (ref "U2") (pin "44") (pinfunction "GND_44") (pintype "passive"))
      (node (ref "WIFI") (pin "1") (pinfunction "GND_1") (pintype "passive"))
      (node (ref "ZD1") (pin "A") (pintype "passive"))
      (node (ref "ZD10") (pin "A") (pintype "passive"))
      (node (ref "ZD2") (pin "A") (pintype "passive"))
      (node (ref "ZD3") (pin "A") (pintype "passive"))
      (node (ref "ZD4") (pin "A") (pintype "passive"))
      (node (ref "ZD5") (pin "A") (pintype "passive"))
      (node (ref "ZD6") (pin "A") (pintype "passive"))
      (node (ref "ZD7") (pin "A") (pintype "passive"))
      (node (ref "ZD8") (pin "A") (pintype "passive"))
      (node (ref "ZD9") (pin "A") (pintype "passive"))
    )
    (net (code "92") (name "Net-(BAT1-Pad1)") (class "Default")
      (node (ref "BAT1") (pin "1") (pinfunction "1_1") (pintype "passive"))
      (node (ref "D1") (pin "A") (pintype "passive"))
    )
    (net (code "93") (name "Net-(BAT1-Pad2)") (class "Default")
      (node (ref "BAT1") (pin "2") (pinfunction "2_2") (pintype "passive"))
      (node (ref "R1") (pin "1") (pintype "passive"))
    )
    (net (code "94") (name "Net-(BUZ1-Pad2)") (class "Default")
      (node (ref "BUZ1") (pin "2") (pinfunction "2_2") (pintype "passive"))
      (node (ref "R15") (pin "2") (pintype "passive"))
    )
    (net (code "95") (name "Net-(C14-Pad2)") (class "Default")
      (node (ref "C14") (pin "2") (pintype "passive"))
      (node (ref "D4") (pin "K") (pintype "passive"))
      (node (ref "R12") (pin "2") (pintype "passive"))
      (node (ref "R13") (pin "2") (pintype "passive"))
    )
    (net (code "96") (name "Net-(C23-Pad1)") (class "Default")
      (node (ref "C23") (pin "1") (pintype "passive"))
      (node (ref "R8") (pin "1") (pinfunction "1_1") (pintype "passive"))
      (node (ref "ZD11") (pin "A") (pintype "passive"))
    )
    (net (code "97") (name "Net-(C27-Pad1)") (class "Default")
      (node (ref "C27") (pin "1") (pinfunction "1_1") (pintype "passive"))
      (node (ref "EC5") (pin "1") (pinfunction "1_1") (pintype "passive"))
      (node (ref "R17") (pin "1") (pinfunction "1_1") (pintype "passive"))
      (node (ref "REC1") (pin "1") (pinfunction "1_1") (pintype "passive"))
    )
    (net (code "98") (name "Net-(P3-Pad1)") (class "Default")
      (node (ref "P3") (pin "1") (pinfunction "1_1") (pintype "passive"))
      (node (ref "R10") (pin "1") (pinfunction "1_1") (pintype "passive"))
      (node (ref "R11") (pin "1") (pinfunction "1_1") (pintype "passive"))
    )
    (net (code "99") (name "Net-(P3-Pad4)") (class "Default")
      (node (ref "P3") (pin "4") (pinfunction "4_4") (pintype "passive"))
      (node (ref "R18") (pin "1") (pinfunction "1_1") (pintype "passive"))
      (node (ref "R5") (pin "1") (pinfunction "1_1") (pintype "passive"))
    )
    (net (code "100") (name "Net-(Q2-PadB)") (class "Default")
      (node (ref "Q2") (pin "B") (pintype "passive"))
      (node (ref "R12") (pin "1") (pintype "passive"))
    )
    (net (code "101") (name "Net-(Q3-PadB)") (class "Default")
      (node (ref "Q3") (pin "B") (pintype "passive"))
      (node (ref "R14") (pin "2") (pinfunction "2_2") (pintype "passive"))
      (node (ref "R8") (pin "2") (pinfunction "2_2") (pintype "passive"))
    )
    (net (code "102") (name "Net-(Q8-PadB)") (class "Default")
      (node (ref "Q8") (pin "B") (pintype "passive"))
      (node (ref "R49") (pin "2") (pintype "passive"))
    )
    (net (code "103") (name "Net-(Q9-PadB)") (class "Default")
      (node (ref "Q9") (pin "B") (pintype "passive"))
      (node (ref "R46") (pin "2") (pintype "passive"))
    )
    (net (code "104") (name "Net-(Q10-PadB)") (class "Default")
      (node (ref "Q10") (pin "B") (pintype "passive"))
      (node (ref "R50") (pin "2") (pintype "passive"))
    )
    (net (code "105") (name "Net-(WIFI-HM1)") (class "Default")
      (node (ref "R45") (pin "2") (pinfunction "2_2") (pintype "passive"))
      (node (ref "WIFI") (pin "20") (pinfunction "HM1_20") (pintype "passive"))
    )
    (net (code "106") (name "Net-(WIFI-RESET)") (class "Default")
      (node (ref "R44") (pin "1") (pinfunction "1_1") (pintype "passive"))
      (node (ref "WIFI") (pin "30") (pinfunction "RESET_30") (pintype "passive"))
    )
    (net (code "107") (name "unconnected-(LED-Pad32)") (class "Default")
      (node (ref "LED") (pin "32") (pinfunction "32_32") (pintype "passive+no_connect"))
    )
    (net (code "108") (name "unconnected-(MCU1-P06{slash}SEG23{slash}AN4{slash}EINT4{slash}PWM4CA-Pad31)") (class "Default")
      (node (ref "MCU1") (pin "31") (pinfunction "P06/SEG23/AN4/EINT4/PWM4CA_31") (pintype "passive+no_connect"))
    )
    (net (code "109") (name "unconnected-(MCU1-P07{slash}SEG22{slash}AN5{slash}EINT5{slash}PWM4CB-Pad30)") (class "Default")
      (node (ref "MCU1") (pin "30") (pinfunction "P07/SEG22/AN5/EINT5/PWM4CB_30") (pintype "passive+no_connect"))
    )
    (net (code "110") (name "unconnected-(MCU1-P17{slash}SEG21{slash}AN6{slash}EINT6{slash}SS2-Pad29)") (class "Default")
      (node (ref "MCU1") (pin "29") (pinfunction "P17/SEG21/AN6/EINT6/SS2_29") (pintype "passive+no_connect"))
    )
    (net (code "111") (name "unconnected-(U2-K1-Pad2)") (class "Default")
      (node (ref "U2") (pin "2") (pinfunction "K1_2") (pintype "passive+no_connect"))
    )
    (net (code "112") (name "unconnected-(U2-K2-Pad1)") (class "Default")
      (node (ref "U2") (pin "1") (pinfunction "K2_1") (pintype "passive+no_connect"))
    )
    (net (code "113") (name "unconnected-(U2-SEG16{slash}KS16-Pad22)") (class "Default")
      (node (ref "U2") (pin "22") (pinfunction "SEG16/KS16_22") (pintype "passive+no_connect"))
    )
    (net (code "114") (name "unconnected-(WIFI-GND-Pad9)") (class "Default")
      (node (ref "WIFI") (pin "9") (pinfunction "GND_9") (pintype "passive"))
    )
    (net (code "115") (name "unconnected-(WIFI-GND-Pad25)") (class "Default")
      (node (ref "WIFI") (pin "25") (pinfunction "GND_25") (pintype "passive"))
    )
    (net (code "116") (name "unconnected-(WIFI-GND-Pad32)") (class "Default")
      (node (ref "WIFI") (pin "32") (pinfunction "GND_32") (pintype "passive"))
    )
    (net (code "117") (name "unconnected-(WIFI-Pad3)") (class "Default")
      (node (ref "WIFI") (pin "3") (pintype "passive"))
    )
    (net (code "118") (name "unconnected-(WIFI-Pad5)") (class "Default")
      (node (ref "WIFI") (pin "5") (pintype "passive"))
    )
    (net (code "119") (name "unconnected-(WIFI-Pad6)") (class "Default")
      (node (ref "WIFI") (pin "6") (pintype "passive"))
    )
    (net (code "120") (name "unconnected-(WIFI-Pad7)") (class "Default")
      (node (ref "WIFI") (pin "7") (pintype "passive"))
    )
    (net (code "121") (name "unconnected-(WIFI-Pad8)") (class "Default")
      (node (ref "WIFI") (pin "8") (pintype "passive"))
    )
    (net (code "122") (name "unconnected-(WIFI-Pad10)") (class "Default")
      (node (ref "WIFI") (pin "10") (pintype "passive"))
    )
    (net (code "123") (name "unconnected-(WIFI-Pad11)") (class "Default")
      (node (ref "WIFI") (pin "11") (pintype "passive"))
    )
    (net (code "124") (name "unconnected-(WIFI-Pad14)") (class "Default")
      (node (ref "WIFI") (pin "14") (pintype "passive"))
    )
    (net (code "125") (name "unconnected-(WIFI-Pad15)") (class "Default")
      (node (ref "WIFI") (pin "15") (pintype "passive"))
    )
    (net (code "126") (name "unconnected-(WIFI-Pad16)") (class "Default")
      (node (ref "WIFI") (pin "16") (pintype "passive"))
    )
    (net (code "127") (name "unconnected-(WIFI-Pad17)") (class "Default")
      (node (ref "WIFI") (pin "17") (pintype "passive"))
    )
    (net (code "128") (name "unconnected-(WIFI-Pad19)") (class "Default")
      (node (ref "WIFI") (pin "19") (pintype "passive"))
    )
    (net (code "129") (name "unconnected-(WIFI-Pad21)") (class "Default")
      (node (ref "WIFI") (pin "21") (pintype "passive"))
    )
    (net (code "130") (name "unconnected-(WIFI-Pad22)") (class "Default")
      (node (ref "WIFI") (pin "22") (pintype "passive"))
    )
    (net (code "131") (name "unconnected-(WIFI-Pad23)") (class "Default")
      (node (ref "WIFI") (pin "23") (pintype "passive"))
    )
    (net (code "132") (name "unconnected-(WIFI-Pad24)") (class "Default")
      (node (ref "WIFI") (pin "24") (pintype "passive"))
    )
    (net (code "133") (name "unconnected-(WIFI-Pad27)") (class "Default")
      (node (ref "WIFI") (pin "27") (pintype "passive"))
    )
    (net (code "134") (name "unconnected-(WIFI-Pad28)") (class "Default")
      (node (ref "WIFI") (pin "28") (pintype "passive"))
    )
    (net (code "135") (name "unconnected-(WIFI-Pad29)") (class "Default")
      (node (ref "WIFI") (pin "29") (pintype "passive"))
    )
    (net (code "136") (name "unconnected-(WIFI-Pad31)") (class "Default")
      (node (ref "WIFI") (pin "31") (pintype "passive"))
    )
    (net (code "137") (name "unconnected-(WIFI-Pad33)") (class "Default")
      (node (ref "WIFI") (pin "33") (pintype "passive"))
    )
    (net (code "138") (name "unconnected-(WIFI-VCC-Pad2)") (class "Default")
      (node (ref "WIFI") (pin "2") (pinfunction "VCC_2") (pintype "passive"))
    )
    (net (code "139") (name "unconnected-(WIFI-VCC-Pad13)") (class "Default")
      (node (ref "WIFI") (pin "13") (pinfunction "VCC_13") (pintype "passive"))
    )
  )
)
